# VREF.net
KiCad netlist of a schematic drawn in Altium Designer
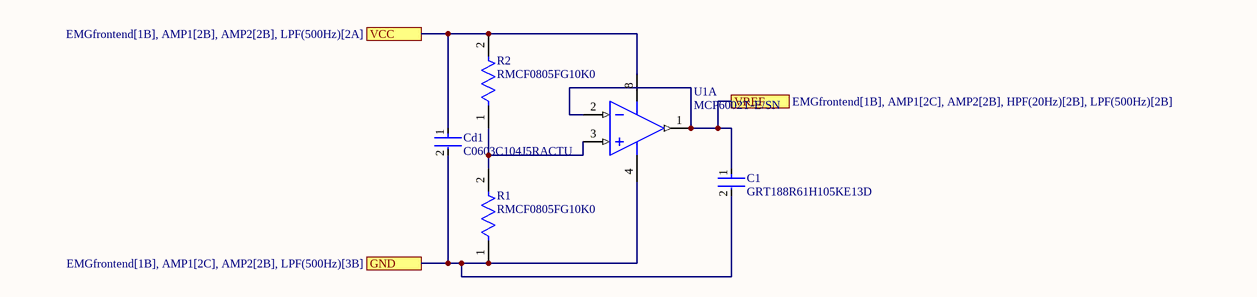
[diagram p0: VREF.SchDoc]

(export (version "E")
  (design (tool "Eeschema 10.0.6"))
  (components
    (comp (ref "C1")
      (value "GRT188R61H105KE13D")
      (footprint "FP-GRT188-0_1-e0_2_0_5-IPC_B")
      (description "Multi-Layer Ceramic Capacitor 1uF 50V X5R ±10% 0603 Paper T/R")
      (fields (field (name "TOLERANCE") "10%"))
      (libsource (lib "Altium Content Vault") (part "02cd4be3c70576c341d710602a673aa"))
    )
    (comp (ref "Cd1")
      (value "C0603C104J5RACTU")
      (footprint "FP-C0603C-CF-MFG")
      (description "CAP CER 0.1UF 50V 5% X7R 0603")
      (fields
        (field (name "TOLERANCE") "0.05")
        (field (name "OCTOPART") "https://octopart.com/c0603c104j5ractu-kemet-10440638")
      )
      (libsource (lib "Altium Content Vault") (part "b4654b650e69147ec39a6b967a45e02"))
    )
    (comp (ref "R1")
      (value "RMCF0805FG10K0")
      (footprint "FP-RMCF0805-IPC_A")
      (description "10kΩ ±1% 0.125W 0805 Thick Film Chip Resistor AEC-Q200 compliant")
      (fields (field (name "TOLERANCE") "1%"))
      (libsource (lib "Altium Content Vault") (part "1029c3af85768c4190bb7ad29bc67b5"))
    )
    (comp (ref "R2")
      (value "RMCF0805FG10K0")
      (footprint "FP-RMCF0805-IPC_A")
      (description "10kΩ ±1% 0.125W 0805 Thick Film Chip Resistor AEC-Q200 compliant")
      (fields (field (name "TOLERANCE") "1%"))
      (libsource (lib "Altium Content Vault") (part "1029c3af85768c4190bb7ad29bc67b5"))
    )
    (comp (ref "U1")
      (value "MCP6002T-E/SN")
      (footprint "SOIC-SN8_N")
      (description "None")
      (libsource (lib "Altium Content Vault") (part "AMP-OPA-MCP6002-IL8"))
    )
  )
  (nets
    (net (code "1") (name "/GND") (class "Default")
      (node (ref "C1") (pin "2") (pinfunction "2_2") (pintype "passive"))
      (node (ref "Cd1") (pin "2") (pinfunction "2_2") (pintype "passive"))
      (node (ref "R1") (pin "1") (pinfunction "1_1") (pintype "passive"))
      (node (ref "U1") (pin "4") (pinfunction "VSS_4") (pintype "power_in"))
    )
    (net (code "2") (name "/VCC") (class "Default")
      (node (ref "Cd1") (pin "1") (pinfunction "1_1") (pintype "passive"))
      (node (ref "R2") (pin "2") (pinfunction "2_2") (pintype "passive"))
      (node (ref "U1") (pin "8") (pinfunction "VDD_8") (pintype "power_in"))
    )
    (net (code "3") (name "/VREF") (class "Default")
      (node (ref "C1") (pin "1") (pinfunction "1_1") (pintype "passive"))
      (node (ref "U1") (pin "1") (pinfunction "VOUTA_1") (pintype "output"))
      (node (ref "U1") (pin "2") (pinfunction "VINA-_2") (pintype "input"))
    )
    (net (code "4") (name "Net-(U1A-VINA+)") (class "Default")
      (node (ref "R1") (pin "2") (pinfunction "2_2") (pintype "passive"))
      (node (ref "R2") (pin "1") (pinfunction "1_1") (pintype "passive"))
      (node (ref "U1") (pin "3") (pinfunction "VINA+_3") (pintype "input"))
    )
  )
)
